# SunS_ALS_Interface_Pull_Ups.net
KiCad netlist of a schematic drawn in Altium Designer
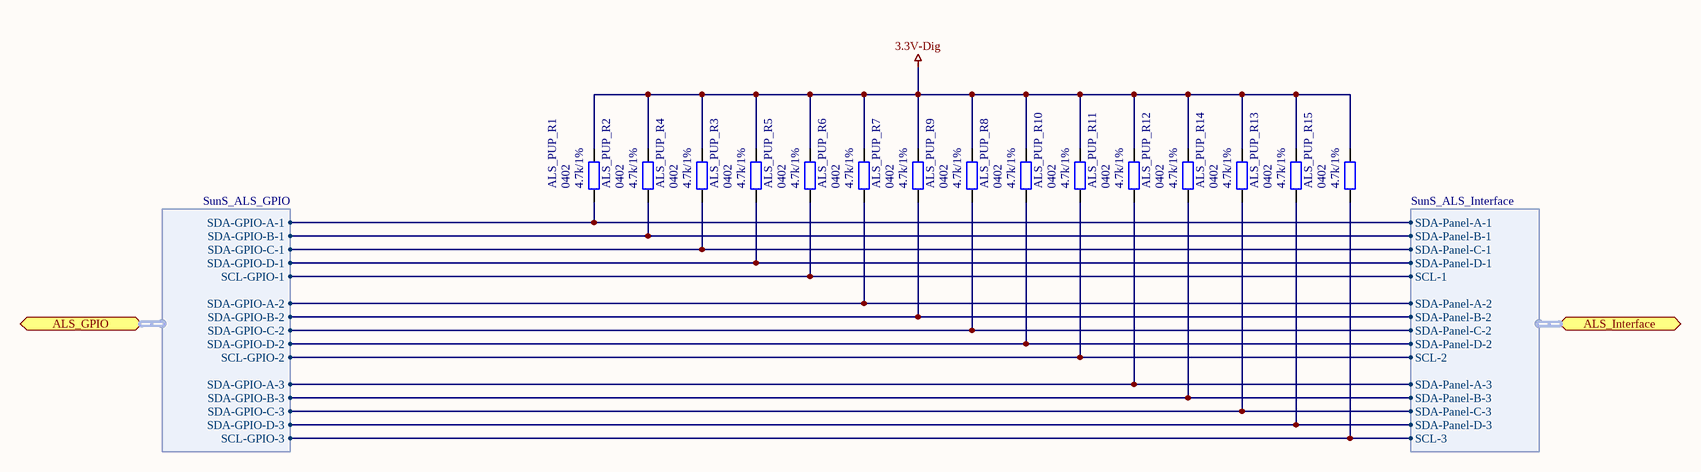
[diagram p0: SunS_ALS_Interface_Pull_Ups.SchDoc]

(export (version "E")
  (design (tool "Eeschema 10.0.6"))
  (components
    (comp (ref "ALS_PUP_R1")
      (value "4.7k/1%")
      (footprint "SMD_Resistor_0402")
      (description "4.7k/1% Vishay CRCW 0402 Resistor. 63mW, 100ppm, 50V.")
      (fields
        (field (name "MANUFACTURERPARTNUMBER") "CRCW04024K70FKxxxx")
        (field (name "MANUFACTURER") "Vishay")
        (field (name "PACKAGE") "0402")
      )
      (libsource (lib "resistors") (part "CRCW04024K70FKxxxx"))
    )
    (comp (ref "ALS_PUP_R2")
      (value "4.7k/1%")
      (footprint "SMD_Resistor_0402")
      (description "4.7k/1% Vishay CRCW 0402 Resistor. 63mW, 100ppm, 50V.")
      (fields
        (field (name "MANUFACTURERPARTNUMBER") "CRCW04024K70FKxxxx")
        (field (name "MANUFACTURER") "Vishay")
        (field (name "PACKAGE") "0402")
      )
      (libsource (lib "resistors") (part "CRCW04024K70FKxxxx"))
    )
    (comp (ref "ALS_PUP_R3")
      (value "4.7k/1%")
      (footprint "SMD_Resistor_0402")
      (description "4.7k/1% Vishay CRCW 0402 Resistor. 63mW, 100ppm, 50V.")
      (fields
        (field (name "MANUFACTURERPARTNUMBER") "CRCW04024K70FKxxxx")
        (field (name "MANUFACTURER") "Vishay")
        (field (name "PACKAGE") "0402")
      )
      (libsource (lib "resistors") (part "CRCW04024K70FKxxxx"))
    )
    (comp (ref "ALS_PUP_R4")
      (value "4.7k/1%")
      (footprint "SMD_Resistor_0402")
      (description "4.7k/1% Vishay CRCW 0402 Resistor. 63mW, 100ppm, 50V.")
      (fields
        (field (name "MANUFACTURERPARTNUMBER") "CRCW04024K70FKxxxx")
        (field (name "MANUFACTURER") "Vishay")
        (field (name "PACKAGE") "0402")
      )
      (libsource (lib "resistors") (part "CRCW04024K70FKxxxx"))
    )
    (comp (ref "ALS_PUP_R5")
      (value "4.7k/1%")
      (footprint "SMD_Resistor_0402")
      (description "4.7k/1% Vishay CRCW 0402 Resistor. 63mW, 100ppm, 50V.")
      (fields
        (field (name "MANUFACTURERPARTNUMBER") "CRCW04024K70FKxxxx")
        (field (name "MANUFACTURER") "Vishay")
        (field (name "PACKAGE") "0402")
      )
      (libsource (lib "resistors") (part "CRCW04024K70FKxxxx"))
    )
    (comp (ref "ALS_PUP_R6")
      (value "4.7k/1%")
      (footprint "SMD_Resistor_0402")
      (description "4.7k/1% Vishay CRCW 0402 Resistor. 63mW, 100ppm, 50V.")
      (fields
        (field (name "MANUFACTURERPARTNUMBER") "CRCW04024K70FKxxxx")
        (field (name "MANUFACTURER") "Vishay")
        (field (name "PACKAGE") "0402")
      )
      (libsource (lib "resistors") (part "CRCW04024K70FKxxxx"))
    )
    (comp (ref "ALS_PUP_R7")
      (value "4.7k/1%")
      (footprint "SMD_Resistor_0402")
      (description "4.7k/1% Vishay CRCW 0402 Resistor. 63mW, 100ppm, 50V.")
      (fields
        (field (name "MANUFACTURERPARTNUMBER") "CRCW04024K70FKxxxx")
        (field (name "MANUFACTURER") "Vishay")
        (field (name "PACKAGE") "0402")
      )
      (libsource (lib "resistors") (part "CRCW04024K70FKxxxx"))
    )
    (comp (ref "ALS_PUP_R8")
      (value "4.7k/1%")
      (footprint "SMD_Resistor_0402")
      (description "4.7k/1% Vishay CRCW 0402 Resistor. 63mW, 100ppm, 50V.")
      (fields
        (field (name "MANUFACTURERPARTNUMBER") "CRCW04024K70FKxxxx")
        (field (name "MANUFACTURER") "Vishay")
        (field (name "PACKAGE") "0402")
      )
      (libsource (lib "resistors") (part "CRCW04024K70FKxxxx"))
    )
    (comp (ref "ALS_PUP_R9")
      (value "4.7k/1%")
      (footprint "SMD_Resistor_0402")
      (description "4.7k/1% Vishay CRCW 0402 Resistor. 63mW, 100ppm, 50V.")
      (fields
        (field (name "MANUFACTURERPARTNUMBER") "CRCW04024K70FKxxxx")
        (field (name "MANUFACTURER") "Vishay")
        (field (name "PACKAGE") "0402")
      )
      (libsource (lib "resistors") (part "CRCW04024K70FKxxxx"))
    )
    (comp (ref "ALS_PUP_R10")
      (value "4.7k/1%")
      (footprint "SMD_Resistor_0402")
      (description "4.7k/1% Vishay CRCW 0402 Resistor. 63mW, 100ppm, 50V.")
      (fields
        (field (name "MANUFACTURERPARTNUMBER") "CRCW04024K70FKxxxx")
        (field (name "MANUFACTURER") "Vishay")
        (field (name "PACKAGE") "0402")
      )
      (libsource (lib "resistors") (part "CRCW04024K70FKxxxx"))
    )
    (comp (ref "ALS_PUP_R11")
      (value "4.7k/1%")
      (footprint "SMD_Resistor_0402")
      (description "4.7k/1% Vishay CRCW 0402 Resistor. 63mW, 100ppm, 50V.")
      (fields
        (field (name "MANUFACTURERPARTNUMBER") "CRCW04024K70FKxxxx")
        (field (name "MANUFACTURER") "Vishay")
        (field (name "PACKAGE") "0402")
      )
      (libsource (lib "resistors") (part "CRCW04024K70FKxxxx"))
    )
    (comp (ref "ALS_PUP_R12")
      (value "4.7k/1%")
      (footprint "SMD_Resistor_0402")
      (description "4.7k/1% Vishay CRCW 0402 Resistor. 63mW, 100ppm, 50V.")
      (fields
        (field (name "MANUFACTURERPARTNUMBER") "CRCW04024K70FKxxxx")
        (field (name "MANUFACTURER") "Vishay")
        (field (name "PACKAGE") "0402")
      )
      (libsource (lib "resistors") (part "CRCW04024K70FKxxxx"))
    )
    (comp (ref "ALS_PUP_R13")
      (value "4.7k/1%")
      (footprint "SMD_Resistor_0402")
      (description "4.7k/1% Vishay CRCW 0402 Resistor. 63mW, 100ppm, 50V.")
      (fields
        (field (name "MANUFACTURERPARTNUMBER") "CRCW04024K70FKxxxx")
        (field (name "MANUFACTURER") "Vishay")
        (field (name "PACKAGE") "0402")
      )
      (libsource (lib "resistors") (part "CRCW04024K70FKxxxx"))
    )
    (comp (ref "ALS_PUP_R14")
      (value "4.7k/1%")
      (footprint "SMD_Resistor_0402")
      (description "4.7k/1% Vishay CRCW 0402 Resistor. 63mW, 100ppm, 50V.")
      (fields
        (field (name "MANUFACTURERPARTNUMBER") "CRCW04024K70FKxxxx")
        (field (name "MANUFACTURER") "Vishay")
        (field (name "PACKAGE") "0402")
      )
      (libsource (lib "resistors") (part "CRCW04024K70FKxxxx"))
    )
    (comp (ref "ALS_PUP_R15")
      (value "4.7k/1%")
      (footprint "SMD_Resistor_0402")
      (description "4.7k/1% Vishay CRCW 0402 Resistor. 63mW, 100ppm, 50V.")
      (fields
        (field (name "MANUFACTURERPARTNUMBER") "CRCW04024K70FKxxxx")
        (field (name "MANUFACTURER") "Vishay")
        (field (name "PACKAGE") "0402")
      )
      (libsource (lib "resistors") (part "CRCW04024K70FKxxxx"))
    )
  )
  (nets
    (net (code "3") (name "/SCL-1") (class "Default")
      (node (ref "ALS_PUP_R5") (pin "2") (pinfunction "2_2") (pintype "passive"))
    )
    (net (code "4") (name "/SCL-2") (class "Default")
      (node (ref "ALS_PUP_R10") (pin "2") (pinfunction "2_2") (pintype "passive"))
    )
    (net (code "5") (name "/SCL-3") (class "Default")
      (node (ref "ALS_PUP_R15") (pin "2") (pinfunction "2_2") (pintype "passive"))
    )
    (net (code "6") (name "/SDA-GPIO-A-1") (class "Default")
      (node (ref "ALS_PUP_R1") (pin "2") (pinfunction "2_2") (pintype "passive"))
    )
    (net (code "7") (name "/SDA-GPIO-A-2") (class "Default")
      (node (ref "ALS_PUP_R6") (pin "2") (pinfunction "2_2") (pintype "passive"))
    )
    (net (code "8") (name "/SDA-GPIO-A-3") (class "Default")
      (node (ref "ALS_PUP_R11") (pin "2") (pinfunction "2_2") (pintype "passive"))
    )
    (net (code "9") (name "/SDA-GPIO-B-1") (class "Default")
      (node (ref "ALS_PUP_R2") (pin "2") (pinfunction "2_2") (pintype "passive"))
    )
    (net (code "10") (name "/SDA-GPIO-B-2") (class "Default")
      (node (ref "ALS_PUP_R7") (pin "2") (pinfunction "2_2") (pintype "passive"))
    )
    (net (code "11") (name "/SDA-GPIO-B-3") (class "Default")
      (node (ref "ALS_PUP_R12") (pin "2") (pinfunction "2_2") (pintype "passive"))
    )
    (net (code "12") (name "/SDA-GPIO-C-1") (class "Default")
      (node (ref "ALS_PUP_R4") (pin "2") (pinfunction "2_2") (pintype "passive"))
    )
    (net (code "13") (name "/SDA-GPIO-C-2") (class "Default")
      (node (ref "ALS_PUP_R9") (pin "2") (pinfunction "2_2") (pintype "passive"))
    )
    (net (code "14") (name "/SDA-GPIO-C-3") (class "Default")
      (node (ref "ALS_PUP_R14") (pin "2") (pinfunction "2_2") (pintype "passive"))
    )
    (net (code "15") (name "/SDA-GPIO-D-1") (class "Default")
      (node (ref "ALS_PUP_R3") (pin "2") (pinfunction "2_2") (pintype "passive"))
    )
    (net (code "16") (name "/SDA-GPIO-D-2") (class "Default")
      (node (ref "ALS_PUP_R8") (pin "2") (pinfunction "2_2") (pintype "passive"))
    )
    (net (code "17") (name "/SDA-GPIO-D-3") (class "Default")
      (node (ref "ALS_PUP_R13") (pin "2") (pinfunction "2_2") (pintype "passive"))
    )
    (net (code "20") (name "3.3V-Dig") (class "Default")
      (node (ref "ALS_PUP_R1") (pin "1") (pinfunction "1_1") (pintype "passive"))
      (node (ref "ALS_PUP_R10") (pin "1") (pinfunction "1_1") (pintype "passive"))
      (node (ref "ALS_PUP_R11") (pin "1") (pinfunction "1_1") (pintype "passive"))
      (node (ref "ALS_PUP_R12") (pin "1") (pinfunction "1_1") (pintype "passive"))
      (node (ref "ALS_PUP_R13") (pin "1") (pinfunction "1_1") (pintype "passive"))
      (node (ref "ALS_PUP_R14") (pin "1") (pinfunction "1_1") (pintype "passive"))
      (node (ref "ALS_PUP_R15") (pin "1") (pinfunction "1_1") (pintype "passive"))
      (node (ref "ALS_PUP_R2") (pin "1") (pinfunction "1_1") (pintype "passive"))
      (node (ref "ALS_PUP_R3") (pin "1") (pinfunction "1_1") (pintype "passive"))
      (node (ref "ALS_PUP_R4") (pin "1") (pinfunction "1_1") (pintype "passive"))
      (node (ref "ALS_PUP_R5") (pin "1") (pinfunction "1_1") (pintype "passive"))
      (node (ref "ALS_PUP_R6") (pin "1") (pinfunction "1_1") (pintype "passive"))
      (node (ref "ALS_PUP_R7") (pin "1") (pinfunction "1_1") (pintype "passive"))
      (node (ref "ALS_PUP_R8") (pin "1") (pinfunction "1_1") (pintype "passive"))
      (node (ref "ALS_PUP_R9") (pin "1") (pinfunction "1_1") (pintype "passive"))
    )
  )
)
